# 12_MSM8916_POWER3.net
KiCad netlist of a schematic drawn in Altium Designer
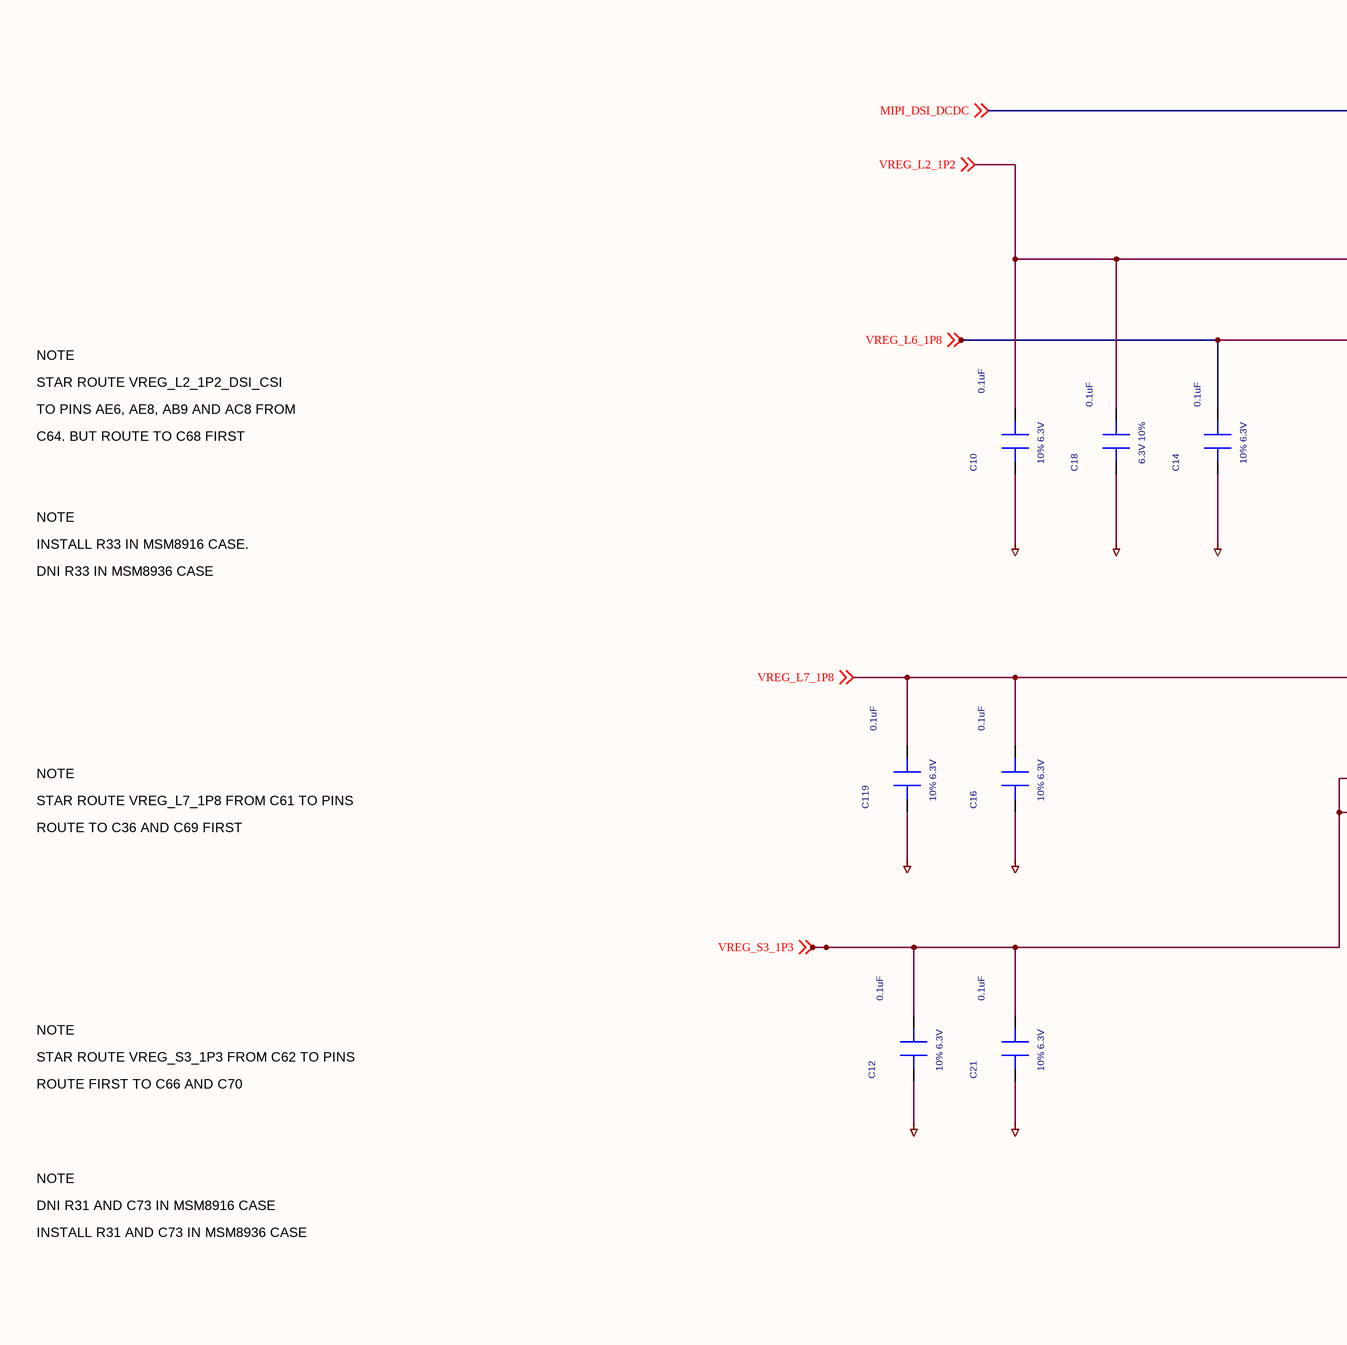
[diagram p0: 12 MSM8916_POWER3.SchDoc, top left]
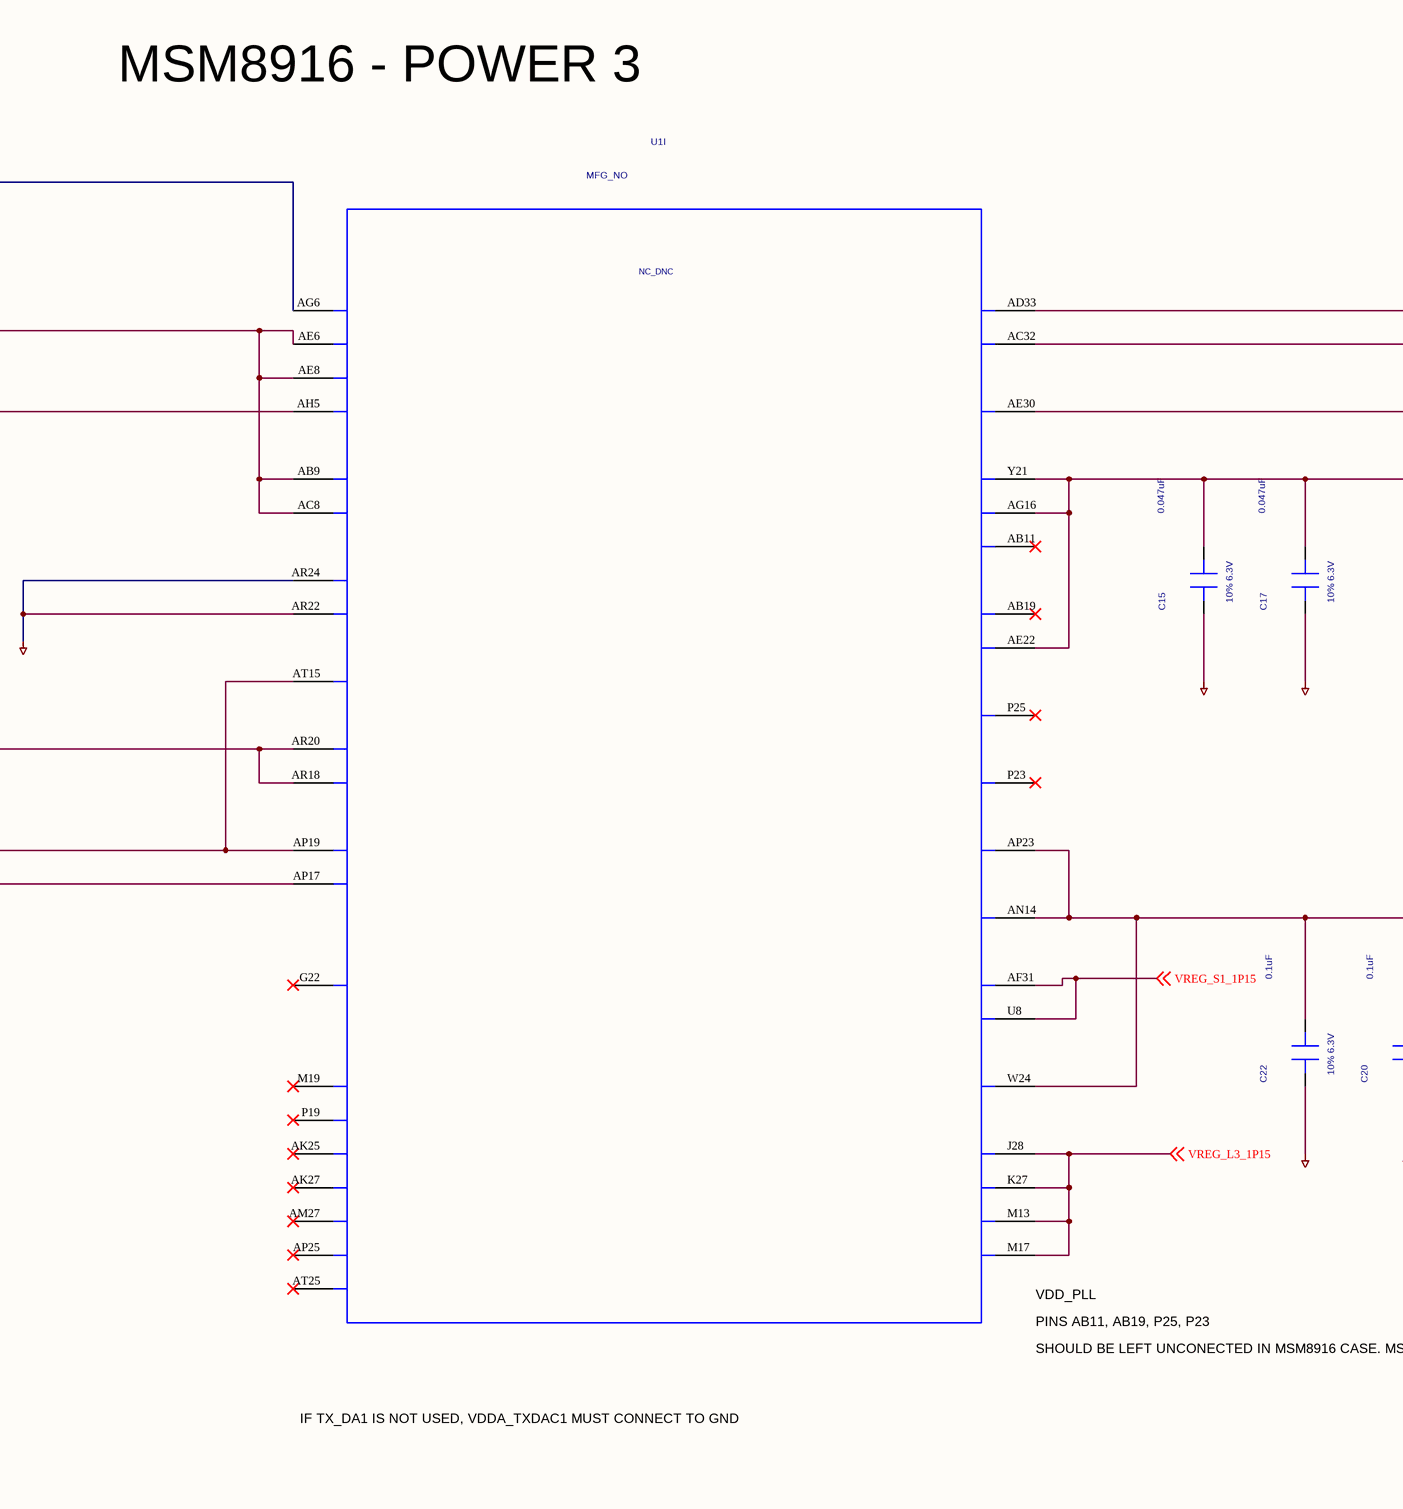
[diagram p1: 12 MSM8916_POWER3.SchDoc, top middle]
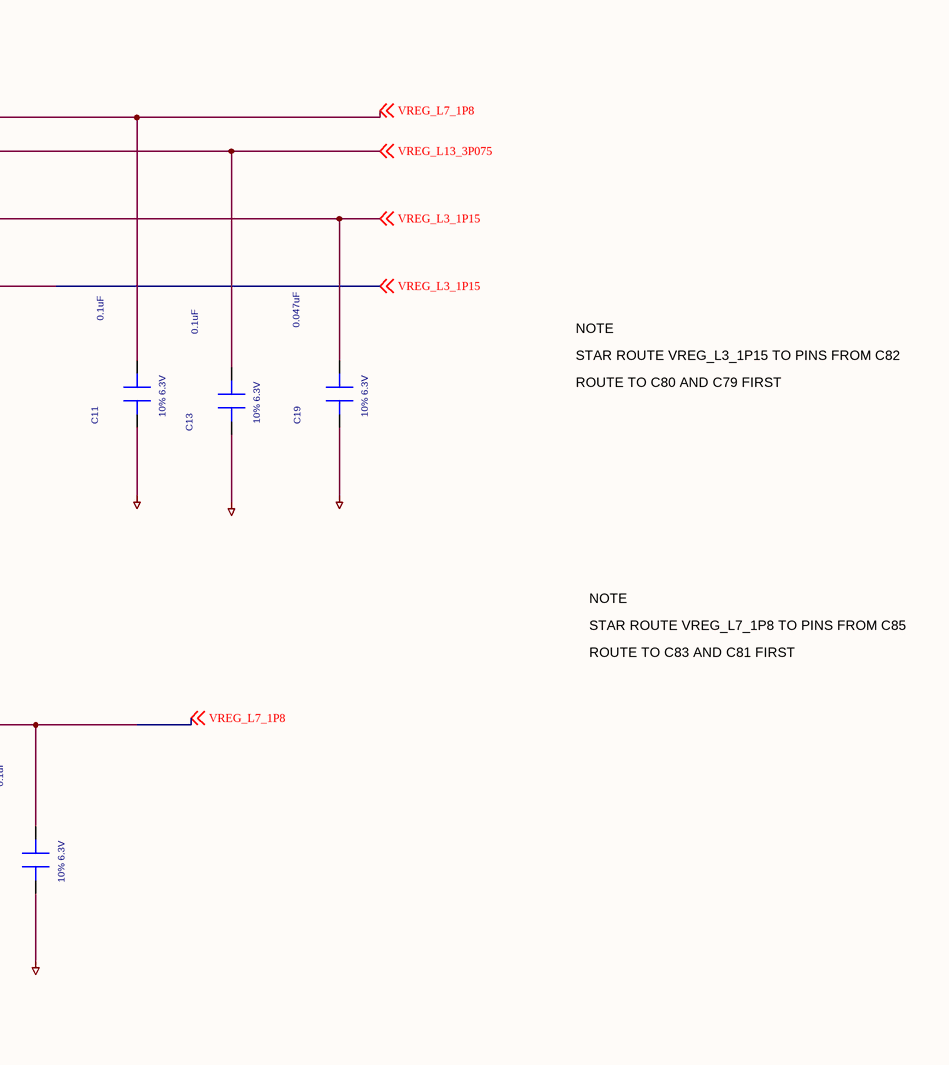
[diagram p2: 12 MSM8916_POWER3.SchDoc, top right]
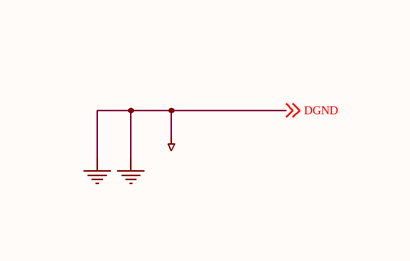
[diagram p3: 12 MSM8916_POWER3.SchDoc, bottom left]
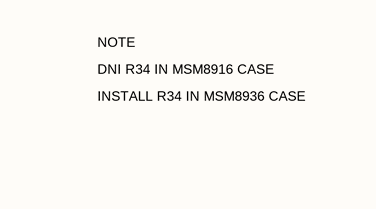
[diagram p4: 12 MSM8916_POWER3.SchDoc, bottom middle]
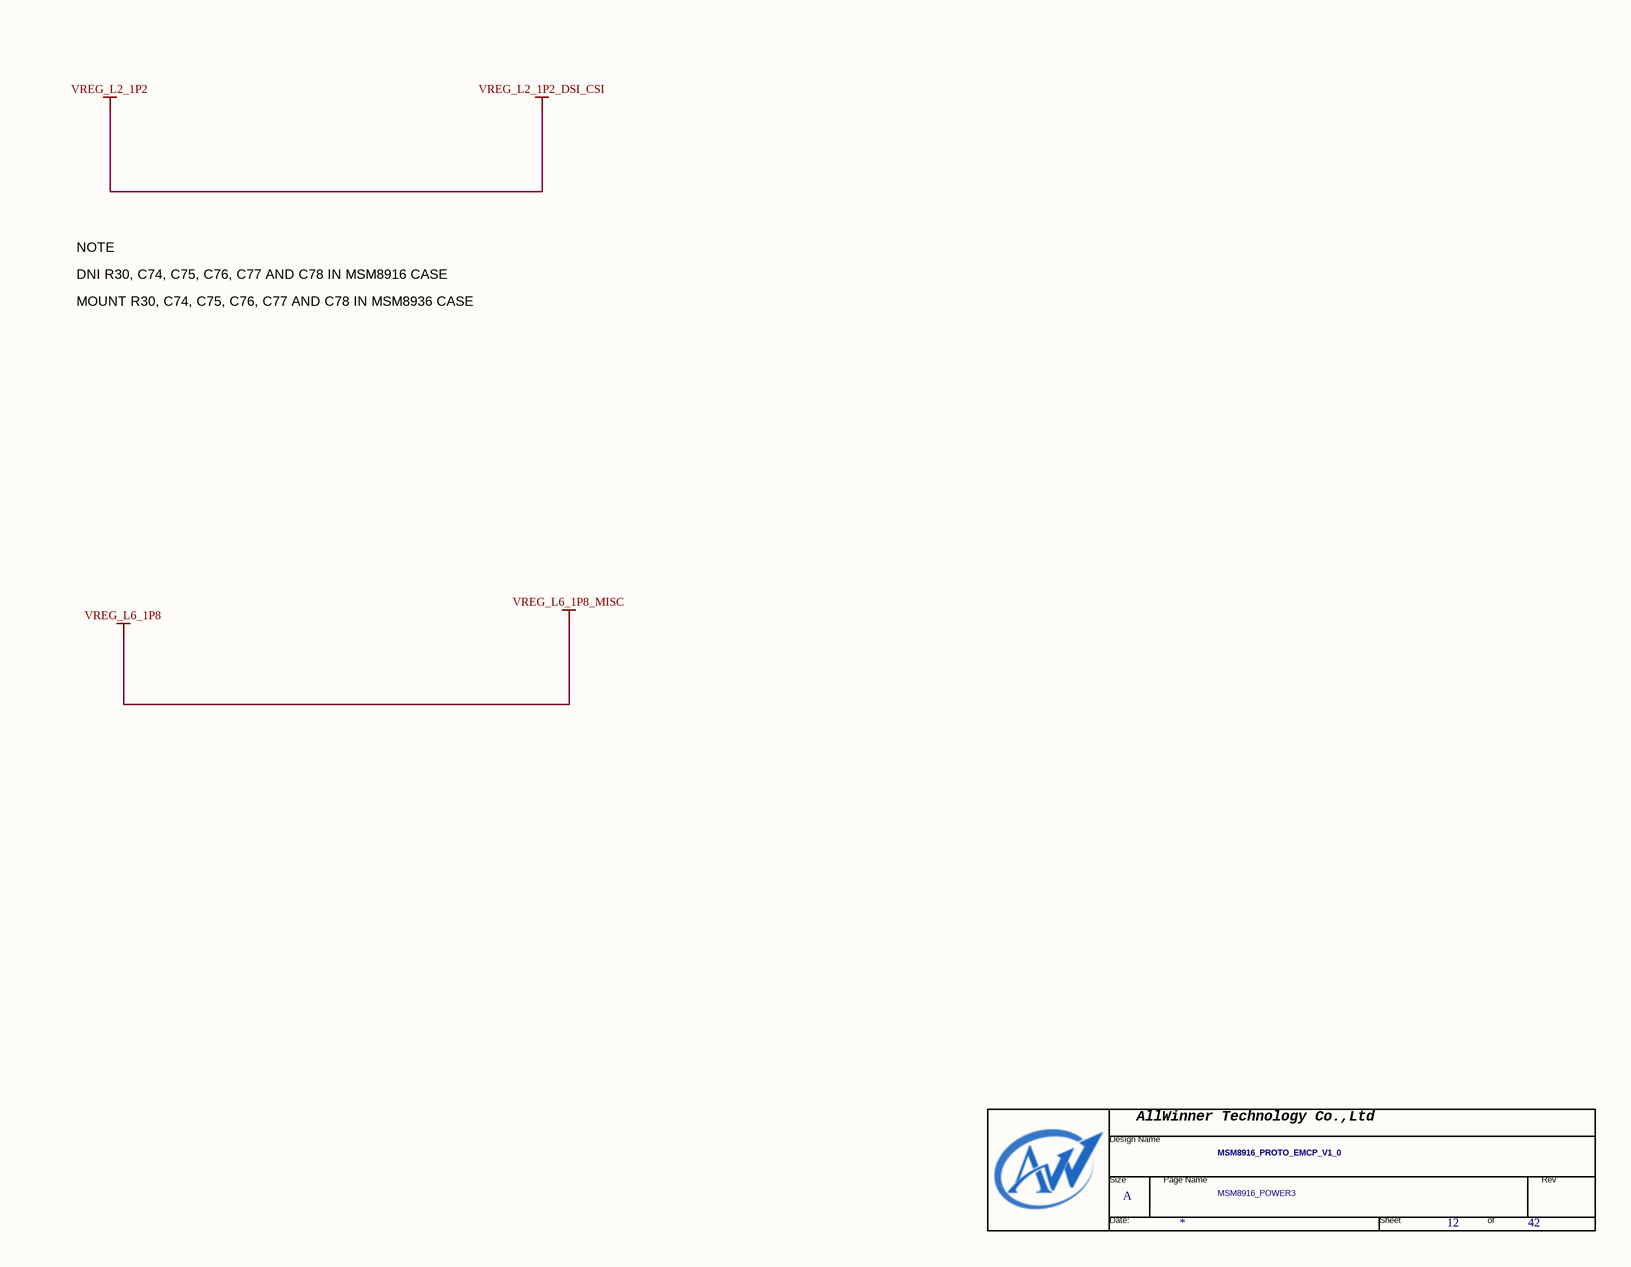
[diagram p5: 12 MSM8916_POWER3.SchDoc, bottom right]

(export (version "E")
  (design (tool "Eeschema 10.0.6"))
  (components
    (comp (ref "*")
      (value "TitleBlock0-AW")
      (fields
        (field (name "PAGE COUNT") "42")
        (field (name "PAGE NUMBER") "12")
        (field (name "PAGE SIZE") "A")
        (field (name "TITLE") "MSM8916_PROTO_EMCP_V1_0")
        (field (name "DOC") "MSM8916_POWER3")
      )
      (libsource (lib "*") (part "TitleBlock0-AW"))
    )
    (comp (ref "C10")
      (value "0.1uF")
      (fields (field (name "TOLERANCE") "10% 6.3V") (field (name "PART_NUMBER") "MCN_NO"))
      (libsource (lib "MSM8916_DRAM_PMIC_REF_Library") (part "CAP#1"))
    )
    (comp (ref "C11")
      (value "0.1uF")
      (fields (field (name "TOLERANCE") "10% 6.3V") (field (name "PART_NUMBER") "MCN_NO"))
      (libsource (lib "MSM8916_DRAM_PMIC_REF_Library") (part "CAP#1"))
    )
    (comp (ref "C12")
      (value "0.1uF")
      (fields (field (name "TOLERANCE") "10% 6.3V") (field (name "PART_NUMBER") "MCN_NO"))
      (libsource (lib "MSM8916_DRAM_PMIC_REF_Library") (part "CAP#1"))
    )
    (comp (ref "C13")
      (value "0.1uF")
      (fields (field (name "TOLERANCE") "10% 6.3V") (field (name "PART_NUMBER") "MCN_NO"))
      (libsource (lib "MSM8916_DRAM_PMIC_REF_Library") (part "CAP#1"))
    )
    (comp (ref "C14")
      (value "0.1uF")
      (fields (field (name "TOLERANCE") "10% 6.3V") (field (name "PART_NUMBER") "MCN_NO"))
      (libsource (lib "MSM8916_DRAM_PMIC_REF_Library") (part "CAP#1"))
    )
    (comp (ref "C15")
      (value "0.047uF")
      (fields (field (name "TOLERANCE") "10% 6.3V") (field (name "PART_NUMBER") "MCN_NO"))
      (libsource (lib "MSM8916_DRAM_PMIC_REF_Library") (part "CAP#1"))
    )
    (comp (ref "C16")
      (value "0.1uF")
      (fields (field (name "TOLERANCE") "10% 6.3V") (field (name "PART_NUMBER") "MCN_NO"))
      (libsource (lib "MSM8916_DRAM_PMIC_REF_Library") (part "CAP#1"))
    )
    (comp (ref "C17")
      (value "0.047uF")
      (fields (field (name "TOLERANCE") "10% 6.3V") (field (name "PART_NUMBER") "MCN_NO"))
      (libsource (lib "MSM8916_DRAM_PMIC_REF_Library") (part "CAP#1"))
    )
    (comp (ref "C18")
      (value "0.1uF")
      (fields (field (name "TOLERANCE") "6.3V 10%") (field (name "PART_NUMBER") "MCN_NO"))
      (libsource (lib "MSM8916_DRAM_PMIC_REF_Library") (part "CAP#1"))
    )
    (comp (ref "C19")
      (value "0.047uF")
      (fields (field (name "TOLERANCE") "10% 6.3V") (field (name "PART_NUMBER") "MCN_NO"))
      (libsource (lib "MSM8916_DRAM_PMIC_REF_Library") (part "CAP#1"))
    )
    (comp (ref "C20")
      (value "0.1uF")
      (fields (field (name "TOLERANCE") "10% 6.3V") (field (name "PART_NUMBER") "MCN_NO"))
      (libsource (lib "MSM8916_DRAM_PMIC_REF_Library") (part "CAP#1"))
    )
    (comp (ref "C21")
      (value "0.1uF")
      (fields (field (name "TOLERANCE") "10% 6.3V") (field (name "PART_NUMBER") "MCN_NO"))
      (libsource (lib "MSM8916_DRAM_PMIC_REF_Library") (part "CAP#1"))
    )
    (comp (ref "C22")
      (value "0.1uF")
      (fields (field (name "TOLERANCE") "10% 6.3V") (field (name "PART_NUMBER") "MCN_NO"))
      (libsource (lib "MSM8916_DRAM_PMIC_REF_Library") (part "CAP#1"))
    )
    (comp (ref "C119")
      (value "0.1uF")
      (fields (field (name "TOLERANCE") "10% 6.3V") (field (name "PART_NUMBER") "MCN_NO"))
      (libsource (lib "MSM8916_DRAM_PMIC_REF_Library") (part "CAP#1"))
    )
    (comp (ref "U1")
      (value "ASIC_MSM8936_760PIN")
      (footprint "MSM-8916-0-760NSP-TR-00-0")
      (fields
        (field (name "SYMNAME") "NC_DNC")
        (field (name "PART_NUMBER") "MCN_NO")
        (field (name "PART_ID") "MFG_NO")
      )
      (libsource (lib "MSM8916_DRAM_PMIC_REF_Library") (part "ASIC_MSM8936_760PIN"))
    )
  )
  (nets
    (net (code "1") (name "DGND") (class "Default")
      (node (ref "C10") (pin "1") (pinfunction "POS_1") (pintype "bidirectional"))
      (node (ref "C11") (pin "1") (pinfunction "POS_1") (pintype "bidirectional"))
      (node (ref "C119") (pin "1") (pinfunction "POS_1") (pintype "bidirectional"))
      (node (ref "C12") (pin "1") (pinfunction "POS_1") (pintype "bidirectional"))
      (node (ref "C13") (pin "1") (pinfunction "POS_1") (pintype "bidirectional"))
      (node (ref "C14") (pin "1") (pinfunction "POS_1") (pintype "bidirectional"))
      (node (ref "C15") (pin "1") (pinfunction "POS_1") (pintype "bidirectional"))
      (node (ref "C16") (pin "1") (pinfunction "POS_1") (pintype "bidirectional"))
      (node (ref "C17") (pin "1") (pinfunction "POS_1") (pintype "bidirectional"))
      (node (ref "C18") (pin "1") (pinfunction "POS_1") (pintype "bidirectional"))
      (node (ref "C19") (pin "1") (pinfunction "POS_1") (pintype "bidirectional"))
      (node (ref "C20") (pin "1") (pinfunction "POS_1") (pintype "bidirectional"))
      (node (ref "C21") (pin "1") (pinfunction "POS_1") (pintype "bidirectional"))
      (node (ref "C22") (pin "1") (pinfunction "POS_1") (pintype "bidirectional"))
      (node (ref "U1") (pin "AR22") (pinfunction "VDDA_TXDAC1_AR22") (pintype "power_in"))
      (node (ref "U1") (pin "AR24") (pinfunction "VDDA_TXDAC0_AR24") (pintype "power_in"))
    )
    (net (code "2") (name "MIPI_DSI_DCDC") (class "Default")
      (node (ref "U1") (pin "AG6") (pinfunction "VDDA_0P4_MIPI_DSI_AG6") (pintype "power_in"))
    )
    (net (code "3") (name "VREG_L2_1P2") (class "Default")
      (node (ref "C10") (pin "2") (pinfunction "NEG_2") (pintype "bidirectional"))
      (node (ref "C18") (pin "2") (pinfunction "NEG_2") (pintype "bidirectional"))
      (node (ref "U1") (pin "AB9") (pinfunction "VDDA_MIPI_CSI_1_AB9") (pintype "power_in"))
      (node (ref "U1") (pin "AC8") (pinfunction "VDDA_MIPI_CSI_2_AC8") (pintype "power_in"))
      (node (ref "U1") (pin "AE6") (pinfunction "VDDA_1P2_MIPI_DSI_1_AE6") (pintype "power_in"))
      (node (ref "U1") (pin "AE8") (pinfunction "VDDA_1P2_MIPI_DSI_2_AE8") (pintype "power_in"))
    )
    (net (code "4") (name "VREG_L3_1P15") (class "Default")
      (node (ref "C15") (pin "2") (pinfunction "NEG_2") (pintype "bidirectional"))
      (node (ref "C17") (pin "2") (pinfunction "NEG_2") (pintype "bidirectional"))
      (node (ref "C19") (pin "2") (pinfunction "NEG_2") (pintype "bidirectional"))
      (node (ref "U1") (pin "AE22") (pinfunction "VDD_SR_MPLL2_GPLL1_AE22") (pintype "power_in"))
      (node (ref "U1") (pin "AE30") (pinfunction "USB2_HS_DVDD_AE30") (pintype "power_in"))
      (node (ref "U1") (pin "AG16") (pinfunction "VDD_SR_GPLL3_AG16") (pintype "power_in"))
      (node (ref "U1") (pin "J28") (pinfunction "VDDA_CDC_EBI0_CA_D0_D1_D2_D3_1_J28") (pintype "power_in"))
      (node (ref "U1") (pin "K27") (pinfunction "VDDA_CDC_EBI0_CA_D0_D1_D2_D3_2_K27") (pintype "power_in"))
      (node (ref "U1") (pin "M13") (pinfunction "VDDA_CDC_EBI0_CA_D0_D1_D2_D3_3_M13") (pintype "power_in"))
      (node (ref "U1") (pin "M17") (pinfunction "VDDA_CDC_EBI0_CA_D0_D1_D2_D3_4_M17") (pintype "power_in"))
      (node (ref "U1") (pin "Y21") (pinfunction "VDD_SR_GPLL0_GPLL2_Y21") (pintype "power_in"))
    )
    (net (code "5") (name "VREG_L6_1P8") (class "Default")
      (node (ref "C14") (pin "2") (pinfunction "NEG_2") (pintype "bidirectional"))
      (node (ref "U1") (pin "AH5") (pinfunction "VDDA_MIPI_DSI_PLL_AH5") (pintype "power_in"))
    )
    (net (code "6") (name "VREG_L7_1P8") (class "Default")
      (node (ref "C11") (pin "2") (pinfunction "NEG_2") (pintype "bidirectional"))
      (node (ref "C119") (pin "2") (pinfunction "NEG_2") (pintype "bidirectional"))
      (node (ref "C16") (pin "2") (pinfunction "NEG_2") (pintype "bidirectional"))
      (node (ref "C20") (pin "2") (pinfunction "NEG_2") (pintype "bidirectional"))
      (node (ref "C22") (pin "2") (pinfunction "NEG_2") (pintype "bidirectional"))
      (node (ref "U1") (pin "AD33") (pinfunction "USB2_HS_VDDA_1P8_AD33") (pintype "power_in"))
      (node (ref "U1") (pin "AN14") (pinfunction "VDD_SR2_PRONTO_PLL_AN14") (pintype "power_in"))
      (node (ref "U1") (pin "AP23") (pinfunction "VDD_SR2_MODEM_PLL1_AP23") (pintype "power_in"))
      (node (ref "U1") (pin "AR18") (pinfunction "VDDAH_BBRX_CH2_AR18") (pintype "power_in"))
      (node (ref "U1") (pin "AR20") (pinfunction "VDDAH_BBRX_CH0_1_AR20") (pintype "power_in"))
      (node (ref "U1") (pin "W24") (pinfunction "VDD_HF_APPS_PLL_W24") (pintype "power_in"))
    )
    (net (code "7") (name "VREG_L13_3P075") (class "Default")
      (node (ref "C13") (pin "2") (pinfunction "NEG_2") (pintype "bidirectional"))
      (node (ref "U1") (pin "AC32") (pinfunction "USB2_HS_VDDA_3P3_AC32") (pintype "power_in"))
    )
    (net (code "8") (name "VREG_S1_1P15") (class "Default")
      (node (ref "U1") (pin "AF31") (pinfunction "VDD_CDC_SDC1_AF31") (pintype "power_in"))
      (node (ref "U1") (pin "U8") (pinfunction "VDD_CDC_SDC2_U8") (pintype "power_in"))
    )
    (net (code "9") (name "VREG_S3_1P3") (class "Default")
      (node (ref "C12") (pin "2") (pinfunction "NEG_2") (pintype "bidirectional"))
      (node (ref "C21") (pin "2") (pinfunction "NEG_2") (pintype "bidirectional"))
      (node (ref "U1") (pin "AP17") (pinfunction "VDDAL_BBRX_CH2_GPSADC_AP17") (pintype "power_in"))
      (node (ref "U1") (pin "AP19") (pinfunction "VDDAL_BBRX_CH0_1_AP19") (pintype "power_in"))
      (node (ref "U1") (pin "AT15") (pinfunction "VDDA_WLAN_AT15") (pintype "power_in"))
    )
    (net (code "10") (name "unconnected-(U1I-VDDA_PLL_1P8-PadG22)") (class "Default")
      (node (ref "U1") (pin "G22") (pinfunction "VDDA_PLL_1P8_G22") (pintype "power_in+no_connect"))
    )
    (net (code "11") (name "unconnected-(U1I-VDD_MSS_1-PadM19)") (class "Default")
      (node (ref "U1") (pin "M19") (pinfunction "VDD_MSS_1_M19") (pintype "power_in+no_connect"))
    )
    (net (code "12") (name "unconnected-(U1I-VDD_MSS_2-PadP19)") (class "Default")
      (node (ref "U1") (pin "P19") (pinfunction "VDD_MSS_2_P19") (pintype "power_in+no_connect"))
    )
    (net (code "13") (name "unconnected-(U1I-VDD_MSS_3-PadAK25)") (class "Default")
      (node (ref "U1") (pin "AK25") (pinfunction "VDD_MSS_3_AK25") (pintype "power_in+no_connect"))
    )
    (net (code "14") (name "unconnected-(U1I-VDD_MSS_4-PadAK27)") (class "Default")
      (node (ref "U1") (pin "AK27") (pinfunction "VDD_MSS_4_AK27") (pintype "power_in+no_connect"))
    )
    (net (code "15") (name "unconnected-(U1I-VDD_MSS_5-PadAM27)") (class "Default")
      (node (ref "U1") (pin "AM27") (pinfunction "VDD_MSS_5_AM27") (pintype "power_in+no_connect"))
    )
    (net (code "16") (name "unconnected-(U1I-VDD_MSS_6-PadAP25)") (class "Default")
      (node (ref "U1") (pin "AP25") (pinfunction "VDD_MSS_6_AP25") (pintype "power_in+no_connect"))
    )
    (net (code "17") (name "unconnected-(U1I-VDD_MSS_7-PadAT25)") (class "Default")
      (node (ref "U1") (pin "AT25") (pinfunction "VDD_MSS_7_AT25") (pintype "power_in+no_connect"))
    )
    (net (code "18") (name "unconnected-(U1I-VDD_SR2_APPS_PLL-PadP25)") (class "Default")
      (node (ref "U1") (pin "P25") (pinfunction "VDD_SR2_APPS_PLL_P25") (pintype "power_in+no_connect"))
    )
    (net (code "19") (name "unconnected-(U1I-VDD_SR2_BIMC_GPLL5-PadP23)") (class "Default")
      (node (ref "U1") (pin "P23") (pinfunction "VDD_SR2_BIMC_GPLL5_P23") (pintype "power_in+no_connect"))
    )
    (net (code "20") (name "unconnected-(U1I-VDD_SR_GPLL4-PadAB11)") (class "Default")
      (node (ref "U1") (pin "AB11") (pinfunction "VDD_SR_GPLL4_AB11") (pintype "power_in+no_connect"))
    )
    (net (code "21") (name "unconnected-(U1I-VDD_SR_MPLL0_GPLL6-PadAB19)") (class "Default")
      (node (ref "U1") (pin "AB19") (pinfunction "VDD_SR_MPLL0_GPLL6_AB19") (pintype "power_in+no_connect"))
    )
  )
)
